# piezo-preamp-tickler_V0-8b.net
KiCad netlist of a schematic drawn in EAGLE
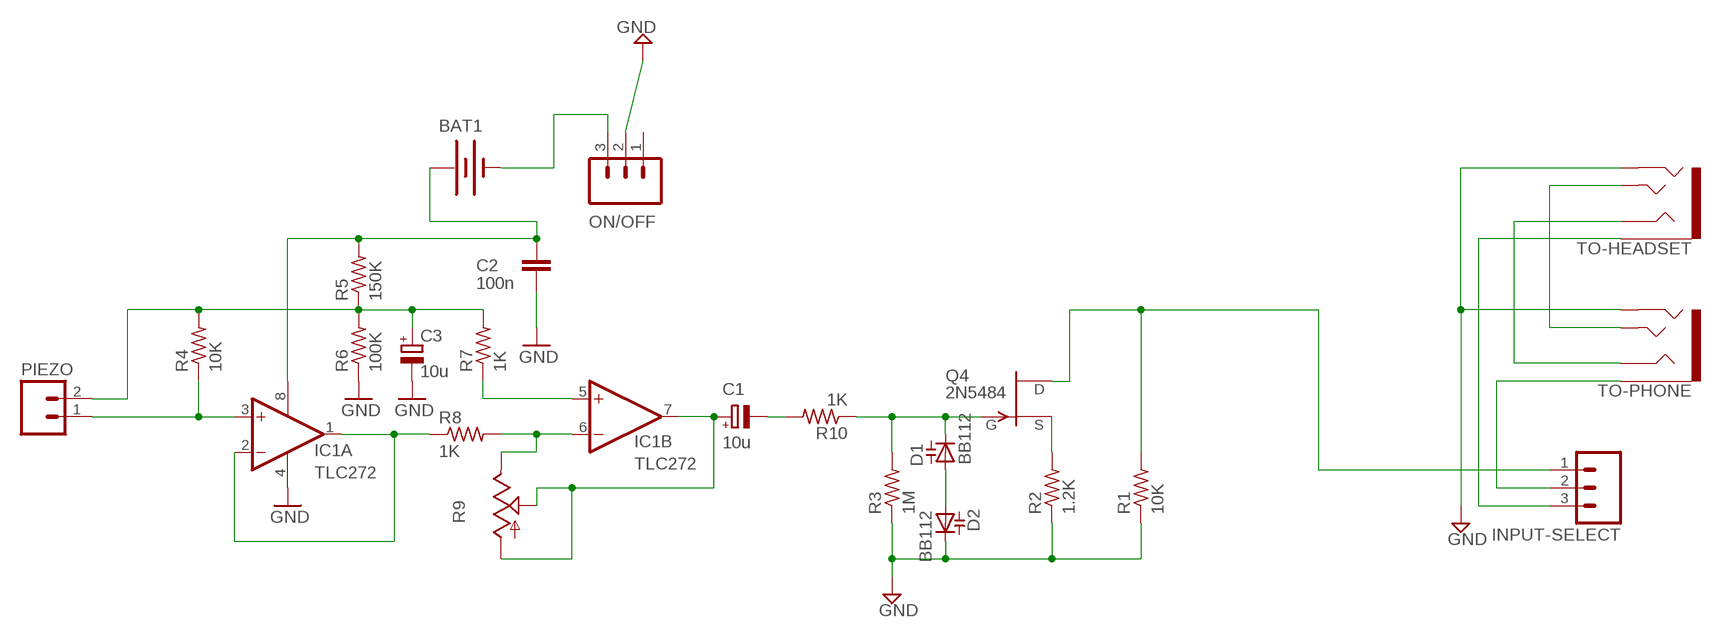
[diagram p0: schematic, sheet 1]

(export (version "E")
  (design (tool "Eeschema 10.0.6"))
  (components
    (comp (ref "BAT1")
      (value "BATTERYA23")
      (footprint "eagle-import:BATTERY-A23")
      (libsource (lib "eagle-import") (part "BATTERYA23"))
    )
    (comp (ref "C1")
      (value "10u")
      (footprint "eagle-import:E2,5-5")
      (libsource (lib "eagle-import") (part "CPOL-EUE2.5-5"))
    )
    (comp (ref "C2")
      (value "100n")
      (footprint "eagle-import:C025-025X050")
      (libsource (lib "eagle-import") (part "C-EU025-025X050"))
    )
    (comp (ref "C3")
      (value "10u")
      (footprint "eagle-import:E2,5-5")
      (libsource (lib "eagle-import") (part "CPOL-EUE2.5-5"))
    )
    (comp (ref "D1")
      (value "BB112")
      (footprint "eagle-import:SOT54H")
      (libsource (lib "eagle-import") (part "BB112"))
    )
    (comp (ref "D2")
      (value "BB112")
      (footprint "eagle-import:SOT54H")
      (libsource (lib "eagle-import") (part "BB112"))
    )
    (comp (ref "IC1")
      (value "TLC272")
      (footprint "eagle-import:DIL08")
      (libsource (lib "eagle-import") (part "TLC272P"))
    )
    (comp (ref "INPUT-SELECT")
      (value "M03SINGLE-POLE-DOUBLE-THROW")
      (footprint "eagle-import:SPDT-SWITCH")
      (libsource (lib "eagle-import") (part "M03SINGLE-POLE-DOUBLE-THROW"))
    )
    (comp (ref "ON/OFF")
      (value "labl")
      (footprint "eagle-import:SPDT-SWITCH")
      (libsource (lib "eagle-import") (part "M03SINGLE-POLE-DOUBLE-THROW"))
    )
    (comp (ref "PIEZO")
      (value "M02LOCK")
      (footprint "eagle-import:1X02_LOCK")
      (libsource (lib "eagle-import") (part "M02LOCK"))
    )
    (comp (ref "Q4")
      (value "2N5484")
      (footprint "eagle-import:TO92-")
      (libsource (lib "eagle-import") (part "?5482N4"))
    )
    (comp (ref "R1")
      (value "10K")
      (footprint "eagle-import:0204V")
      (libsource (lib "eagle-import") (part "R-US_0204/2V"))
    )
    (comp (ref "R2")
      (value "1.2K")
      (footprint "eagle-import:0204V")
      (libsource (lib "eagle-import") (part "R-US_0204/2V"))
    )
    (comp (ref "R3")
      (value "1M")
      (footprint "eagle-import:0204V")
      (libsource (lib "eagle-import") (part "R-US_0204/2V"))
    )
    (comp (ref "R4")
      (value "10K")
      (footprint "eagle-import:0204V")
      (libsource (lib "eagle-import") (part "R-US_0204/2V"))
    )
    (comp (ref "R5")
      (value "150K")
      (footprint "eagle-import:0204V")
      (libsource (lib "eagle-import") (part "R-US_0204/2V"))
    )
    (comp (ref "R6")
      (value "100K")
      (footprint "eagle-import:0204V")
      (libsource (lib "eagle-import") (part "R-US_0204/2V"))
    )
    (comp (ref "R7")
      (value "1K")
      (footprint "eagle-import:0204V")
      (libsource (lib "eagle-import") (part "R-US_0204/2V"))
    )
    (comp (ref "R8")
      (value "1K")
      (footprint "eagle-import:0204V")
      (libsource (lib "eagle-import") (part "R-US_0204/2V"))
    )
    (comp (ref "R9")
      (value "TRIM3386")
      (footprint "eagle-import:TRIM-3386")
      (libsource (lib "eagle-import") (part "TRIM3386"))
    )
    (comp (ref "R10")
      (value "1K")
      (footprint "eagle-import:0204V")
      (libsource (lib "eagle-import") (part "R-US_0204/2V"))
    )
    (comp (ref "TO-HEADSET")
      (value "AUDIO-JACK3LGPADS")
      (footprint "eagle-import:AUDIO-JACK-TRRS-SMD")
      (libsource (lib "eagle-import") (part "AUDIO-JACK3LGPADS"))
    )
    (comp (ref "TO-PHONE")
      (value "AUDIO-JACK3LGPADS")
      (footprint "eagle-import:AUDIO-JACK-TRRS-SMD")
      (libsource (lib "eagle-import") (part "AUDIO-JACK3LGPADS"))
    )
  )
  (nets
    (net (code "1") (name "GND") (class "Default")
      (node (ref "C2") (pin "1") (pinfunction "1_1") (pintype "passive"))
      (node (ref "C3") (pin "-") (pinfunction "-_-") (pintype "passive"))
      (node (ref "D2") (pin "C") (pinfunction "C_C") (pintype "passive"))
      (node (ref "IC1") (pin "4") (pinfunction "V-_4") (pintype "power_in"))
      (node (ref "ON/OFF") (pin "2") (pinfunction "2_2") (pintype "passive"))
      (node (ref "R1") (pin "1") (pinfunction "1_1") (pintype "passive"))
      (node (ref "R2") (pin "1") (pinfunction "1_1") (pintype "passive"))
      (node (ref "R3") (pin "1") (pinfunction "1_1") (pintype "passive"))
      (node (ref "R6") (pin "1") (pinfunction "1_1") (pintype "passive"))
      (node (ref "TO-HEADSET") (pin "RING2") (pinfunction "RING2_RING2") (pintype "bidirectional"))
      (node (ref "TO-PHONE") (pin "RING2") (pinfunction "RING2_RING2") (pintype "bidirectional"))
    )
    (net (code "2") (name "Net-(BAT1-+)") (class "Default")
      (node (ref "BAT1") (pin "PWR@1") (pinfunction "+_PWR@1") (pintype "power_in"))
      (node (ref "C2") (pin "2") (pinfunction "2_2") (pintype "passive"))
      (node (ref "IC1") (pin "8") (pinfunction "V+_8") (pintype "power_in"))
      (node (ref "R5") (pin "2") (pinfunction "2_2") (pintype "passive"))
    )
    (net (code "3") (name "Net-(BAT1--)") (class "Default")
      (node (ref "BAT1") (pin "GND@1") (pinfunction "-_GND@1") (pintype "power_in"))
      (node (ref "ON/OFF") (pin "3") (pinfunction "3_3") (pintype "passive"))
    )
    (net (code "4") (name "Net-(C1-Pad-)") (class "Default")
      (node (ref "C1") (pin "-") (pinfunction "-_-") (pintype "passive"))
      (node (ref "R10") (pin "2") (pinfunction "2_2") (pintype "passive"))
    )
    (net (code "5") (name "Net-(C3-Pad+)") (class "Default")
      (node (ref "C3") (pin "+") (pinfunction "+_+") (pintype "passive"))
      (node (ref "PIEZO") (pin "2") (pinfunction "2_2") (pintype "passive"))
      (node (ref "R4") (pin "2") (pinfunction "2_2") (pintype "passive"))
      (node (ref "R5") (pin "1") (pinfunction "1_1") (pintype "passive"))
      (node (ref "R6") (pin "2") (pinfunction "2_2") (pintype "passive"))
      (node (ref "R7") (pin "2") (pinfunction "2_2") (pintype "passive"))
    )
    (net (code "6") (name "Net-(D1-PadA)") (class "Default")
      (node (ref "D1") (pin "A") (pinfunction "A_A") (pintype "passive"))
      (node (ref "D2") (pin "A") (pinfunction "A_A") (pintype "passive"))
    )
    (net (code "7") (name "Net-(IC1A-+IN)") (class "Default")
      (node (ref "IC1") (pin "3") (pinfunction "+IN_3") (pintype "input"))
      (node (ref "PIEZO") (pin "1") (pinfunction "1_1") (pintype "passive"))
      (node (ref "R4") (pin "1") (pinfunction "1_1") (pintype "passive"))
    )
    (net (code "8") (name "Net-(IC1A--IN)") (class "Default")
      (node (ref "IC1") (pin "1") (pinfunction "OUT_1") (pintype "output"))
      (node (ref "IC1") (pin "2") (pinfunction "-IN_2") (pintype "input"))
      (node (ref "R8") (pin "1") (pinfunction "1_1") (pintype "passive"))
    )
    (net (code "9") (name "Net-(IC1B-+IN)") (class "Default")
      (node (ref "IC1") (pin "5") (pinfunction "+IN_5") (pintype "input"))
      (node (ref "R7") (pin "1") (pinfunction "1_1") (pintype "passive"))
    )
    (net (code "10") (name "Net-(IC1B--IN)") (class "Default")
      (node (ref "IC1") (pin "6") (pinfunction "-IN_6") (pintype "input"))
      (node (ref "R8") (pin "2") (pinfunction "2_2") (pintype "passive"))
      (node (ref "R9") (pin "3") (pinfunction "E_3") (pintype "passive"))
      (node (ref "R9") (pin "6") (pinfunction "E_6") (pintype "passive"))
    )
    (net (code "11") (name "Net-(IC1B-OUT)") (class "Default")
      (node (ref "C1") (pin "+") (pinfunction "+_+") (pintype "passive"))
      (node (ref "IC1") (pin "7") (pinfunction "OUT_7") (pintype "output"))
      (node (ref "R9") (pin "1") (pinfunction "A_1") (pintype "passive"))
      (node (ref "R9") (pin "2") (pinfunction "S_2") (pintype "passive"))
      (node (ref "R9") (pin "4") (pinfunction "A_4") (pintype "passive"))
      (node (ref "R9") (pin "5") (pinfunction "S_5") (pintype "passive"))
    )
    (net (code "12") (name "Net-(INPUT-SELECT-Pad2)") (class "Default")
      (node (ref "INPUT-SELECT") (pin "2") (pinfunction "2_2") (pintype "passive"))
      (node (ref "TO-PHONE") (pin "EARTH") (pinfunction "EARTH_EARTH") (pintype "bidirectional"))
    )
    (net (code "13") (name "Net-(INPUT-SELECT-Pad3)") (class "Default")
      (node (ref "INPUT-SELECT") (pin "3") (pinfunction "3_3") (pintype "passive"))
      (node (ref "TO-HEADSET") (pin "EARTH") (pinfunction "EARTH_EARTH") (pintype "bidirectional"))
    )
    (net (code "14") (name "Net-(Q4-D)") (class "Default")
      (node (ref "INPUT-SELECT") (pin "1") (pinfunction "1_1") (pintype "passive"))
      (node (ref "Q4") (pin "3") (pinfunction "D_3") (pintype "passive"))
      (node (ref "R1") (pin "2") (pinfunction "2_2") (pintype "passive"))
    )
    (net (code "15") (name "Net-(Q4-G)") (class "Default")
      (node (ref "D1") (pin "C") (pinfunction "C_C") (pintype "passive"))
      (node (ref "Q4") (pin "1") (pinfunction "G_1") (pintype "passive"))
      (node (ref "R10") (pin "1") (pinfunction "1_1") (pintype "passive"))
      (node (ref "R3") (pin "2") (pinfunction "2_2") (pintype "passive"))
    )
    (net (code "16") (name "Net-(Q4-S)") (class "Default")
      (node (ref "Q4") (pin "2") (pinfunction "S_2") (pintype "passive"))
      (node (ref "R2") (pin "2") (pinfunction "2_2") (pintype "passive"))
    )
    (net (code "17") (name "Net-(TO-HEADSET-PadRING1)") (class "Default")
      (node (ref "TO-HEADSET") (pin "RING1") (pinfunction "RING1_RING1") (pintype "bidirectional"))
      (node (ref "TO-PHONE") (pin "RING1") (pinfunction "RING1_RING1") (pintype "bidirectional"))
    )
    (net (code "18") (name "Net-(TO-HEADSET-PadTIP)") (class "Default")
      (node (ref "TO-HEADSET") (pin "TIP") (pinfunction "TIP_TIP") (pintype "bidirectional"))
      (node (ref "TO-PHONE") (pin "TIP") (pinfunction "TIP_TIP") (pintype "bidirectional"))
    )
    (net (code "19") (name "unconnected-(ON/OFF-Pad1)") (class "Default")
      (node (ref "ON/OFF") (pin "1") (pinfunction "1_1") (pintype "passive"))
    )
  )
)
